# LP11F7826.net
KiCad netlist of a schematic drawn in EAGLE
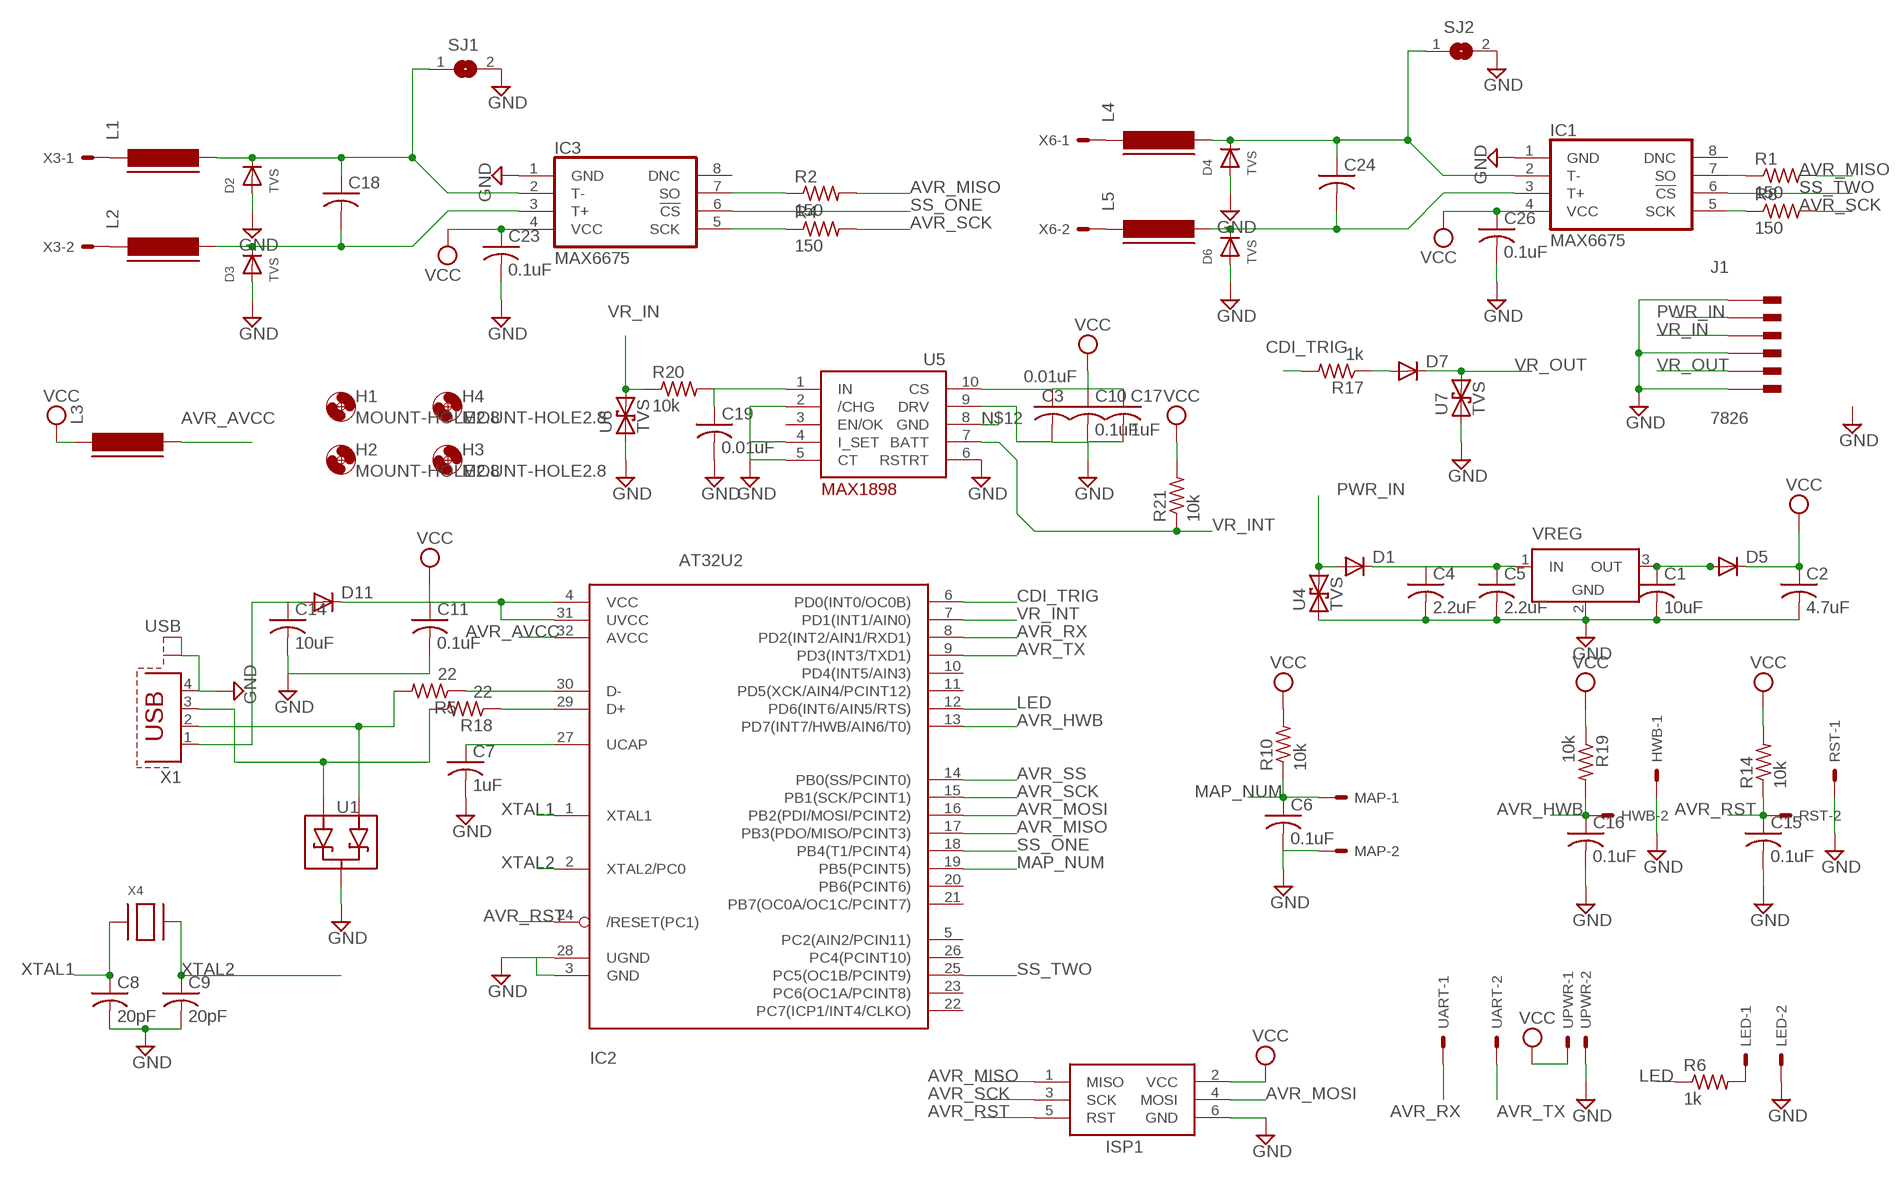
[diagram p0: schematic, sheet 1]

(export (version "E")
  (design (tool "Eeschema 10.0.6"))
  (components
    (comp (ref "C1")
      (value "10uF")
      (footprint "eagle-import:C1206")
      (libsource (lib "eagle-import") (part "C-USC1206"))
    )
    (comp (ref "C2")
      (value "4.7uF")
      (footprint "eagle-import:C1210")
      (libsource (lib "eagle-import") (part "C-USC1210"))
    )
    (comp (ref "C3")
      (value "0.01uF")
      (footprint "eagle-import:C0805")
      (libsource (lib "eagle-import") (part "C-USC0805"))
    )
    (comp (ref "C4")
      (value "2.2uF")
      (footprint "eagle-import:C1206")
      (libsource (lib "eagle-import") (part "C-USC1206"))
    )
    (comp (ref "C5")
      (value "2.2uF")
      (footprint "eagle-import:C1210")
      (libsource (lib "eagle-import") (part "C-USC1210"))
    )
    (comp (ref "C6")
      (value "0.1uF")
      (footprint "eagle-import:C0805")
      (libsource (lib "eagle-import") (part "C-USC0805"))
    )
    (comp (ref "C7")
      (value "1uF")
      (footprint "eagle-import:C0805")
      (libsource (lib "eagle-import") (part "C-USC0805"))
    )
    (comp (ref "C8")
      (value "20pF")
      (footprint "eagle-import:C0805")
      (libsource (lib "eagle-import") (part "C-USC0805"))
    )
    (comp (ref "C9")
      (value "20pF")
      (footprint "eagle-import:C0805")
      (libsource (lib "eagle-import") (part "C-USC0805"))
    )
    (comp (ref "C10")
      (value "0.1uF")
      (footprint "eagle-import:C0805")
      (libsource (lib "eagle-import") (part "C-USC0805"))
    )
    (comp (ref "C11")
      (value "0.1uF")
      (footprint "eagle-import:C0805")
      (libsource (lib "eagle-import") (part "C-USC0805"))
    )
    (comp (ref "C14")
      (value "10uF")
      (footprint "eagle-import:C0805")
      (libsource (lib "eagle-import") (part "C-USC0805"))
    )
    (comp (ref "C15")
      (value "0.1uF")
      (footprint "eagle-import:C0805")
      (libsource (lib "eagle-import") (part "C-USC0805"))
    )
    (comp (ref "C16")
      (value "0.1uF")
      (footprint "eagle-import:C0805")
      (libsource (lib "eagle-import") (part "C-USC0805"))
    )
    (comp (ref "C17")
      (value "1uF")
      (footprint "eagle-import:C0805")
      (libsource (lib "eagle-import") (part "C-USC0805"))
    )
    (comp (ref "C18")
      (value "C-USC0805")
      (footprint "eagle-import:C0805")
      (libsource (lib "eagle-import") (part "C-USC0805"))
    )
    (comp (ref "C19")
      (value "0.01uF")
      (footprint "eagle-import:C0805")
      (libsource (lib "eagle-import") (part "C-USC0805"))
    )
    (comp (ref "C23")
      (value "0.1uF")
      (footprint "eagle-import:C0805")
      (libsource (lib "eagle-import") (part "C-USC0805"))
    )
    (comp (ref "C24")
      (value "C-USC0805")
      (footprint "eagle-import:C0805")
      (libsource (lib "eagle-import") (part "C-USC0805"))
    )
    (comp (ref "C26")
      (value "0.1uF")
      (footprint "eagle-import:C0805")
      (libsource (lib "eagle-import") (part "C-USC0805"))
    )
    (comp (ref "D1")
      (value "CGRM4001-G")
      (footprint "eagle-import:SOD-123_MINI-SMA")
      (libsource (lib "eagle-import") (part "CGRM400-G1"))
    )
    (comp (ref "D2")
      (value "TVS")
      (footprint "eagle-import:SOD-323F")
      (libsource (lib "eagle-import") (part "DIODESOD-323F"))
    )
    (comp (ref "D3")
      (value "TVS")
      (footprint "eagle-import:SOD-323F")
      (libsource (lib "eagle-import") (part "DIODESOD-323F"))
    )
    (comp (ref "D4")
      (value "TVS")
      (footprint "eagle-import:SOD-323F")
      (libsource (lib "eagle-import") (part "DIODESOD-323F"))
    )
    (comp (ref "D5")
      (value "CGRM4001-G")
      (footprint "eagle-import:SOD-123_MINI-SMA")
      (libsource (lib "eagle-import") (part "CGRM400-G1"))
    )
    (comp (ref "D6")
      (value "TVS")
      (footprint "eagle-import:SOD-323F")
      (libsource (lib "eagle-import") (part "DIODESOD-323F"))
    )
    (comp (ref "D7")
      (value "CGRM4001-G")
      (footprint "eagle-import:SOD-123_MINI-SMA")
      (libsource (lib "eagle-import") (part "CGRM400-G1"))
    )
    (comp (ref "D11")
      (value "CGRM4001-G")
      (footprint "eagle-import:SOD-123_MINI-SMA")
      (libsource (lib "eagle-import") (part "CGRM400-G1"))
    )
    (comp (ref "H1")
      (value "MOUNT-HOLE2.8")
      (footprint "eagle-import:2,8")
      (libsource (lib "eagle-import") (part "MOUNT-HOLE2.8"))
    )
    (comp (ref "H2")
      (value "MOUNT-HOLE2.8")
      (footprint "eagle-import:2,8")
      (libsource (lib "eagle-import") (part "MOUNT-HOLE2.8"))
    )
    (comp (ref "H3")
      (value "MOUNT-HOLE2.8")
      (footprint "eagle-import:2,8")
      (libsource (lib "eagle-import") (part "MOUNT-HOLE2.8"))
    )
    (comp (ref "H4")
      (value "MOUNT-HOLE2.8")
      (footprint "eagle-import:2,8")
      (libsource (lib "eagle-import") (part "MOUNT-HOLE2.8"))
    )
    (comp (ref "HWB")
      (value "87758-0216")
      (footprint "eagle-import:87758-0216")
      (fields
        (field (name "MPN") "87758-0216")
        (field (name "OC_FARNELL") "unknown")
        (field (name "OC_NEWARK") "94M1513")
      )
      (libsource (lib "eagle-import") (part "87758-0216"))
    )
    (comp (ref "IC1")
      (value "MAX6675")
      (footprint "eagle-import:SO-8")
      (libsource (lib "eagle-import") (part "IC_MAX31855-SO-8"))
    )
    (comp (ref "IC2")
      (value "AT32U2")
      (footprint "eagle-import:TQFP32-08")
      (libsource (lib "eagle-import") (part "ATMEGA32U2-TQFP"))
    )
    (comp (ref "IC3")
      (value "MAX6675")
      (footprint "eagle-import:SO-8")
      (libsource (lib "eagle-import") (part "IC_MAX31855-SO-8"))
    )
    (comp (ref "ISP1")
      (value "AVRISP-6")
      (footprint "eagle-import:AVRISP")
      (libsource (lib "eagle-import") (part "AVRISP-6"))
    )
    (comp (ref "J1")
      (value "7826")
      (footprint "eagle-import:7806HEADER")
      (libsource (lib "eagle-import") (part "PIN262409-1"))
    )
    (comp (ref "L1")
      (value "FERRITE-0805")
      (footprint "eagle-import:FB805")
      (libsource (lib "eagle-import") (part "FERRITE-0805"))
    )
    (comp (ref "L2")
      (value "FERRITE-0805")
      (footprint "eagle-import:FB805")
      (libsource (lib "eagle-import") (part "FERRITE-0805"))
    )
    (comp (ref "L3")
      (value "FERRITE-0805")
      (footprint "eagle-import:FB805")
      (libsource (lib "eagle-import") (part "FERRITE-0805"))
    )
    (comp (ref "L4")
      (value "FERRITE-0805")
      (footprint "eagle-import:FB805")
      (libsource (lib "eagle-import") (part "FERRITE-0805"))
    )
    (comp (ref "L5")
      (value "FERRITE-0805")
      (footprint "eagle-import:FB805")
      (libsource (lib "eagle-import") (part "FERRITE-0805"))
    )
    (comp (ref "LED")
      (value "87758-0216")
      (footprint "eagle-import:87758-0216")
      (fields
        (field (name "MPN") "87758-0216")
        (field (name "OC_FARNELL") "unknown")
        (field (name "OC_NEWARK") "94M1513")
      )
      (libsource (lib "eagle-import") (part "87758-0216"))
    )
    (comp (ref "MAP")
      (value "87758-0216")
      (footprint "eagle-import:87758-0216")
      (libsource (lib "eagle-import") (part "87758-0216"))
    )
    (comp (ref "R1")
      (value "150")
      (footprint "eagle-import:R0805")
      (libsource (lib "eagle-import") (part "R-US_R0805"))
    )
    (comp (ref "R2")
      (value "150")
      (footprint "eagle-import:R0805")
      (libsource (lib "eagle-import") (part "R-US_R0805"))
    )
    (comp (ref "R4")
      (value "150")
      (footprint "eagle-import:R0805")
      (libsource (lib "eagle-import") (part "R-US_R0805"))
    )
    (comp (ref "R5")
      (value "22")
      (footprint "eagle-import:R0805")
      (libsource (lib "eagle-import") (part "R-US_R0805"))
    )
    (comp (ref "R6")
      (value "1k")
      (footprint "eagle-import:R0805")
      (libsource (lib "eagle-import") (part "R-US_R0805"))
    )
    (comp (ref "R8")
      (value "150")
      (footprint "eagle-import:R0805")
      (libsource (lib "eagle-import") (part "R-US_R0805"))
    )
    (comp (ref "R10")
      (value "10k")
      (footprint "eagle-import:R0805")
      (libsource (lib "eagle-import") (part "R-US_R0805"))
    )
    (comp (ref "R14")
      (value "10k")
      (footprint "eagle-import:R0805")
      (libsource (lib "eagle-import") (part "R-US_R0805"))
    )
    (comp (ref "R17")
      (value "1k")
      (footprint "eagle-import:R0805")
      (libsource (lib "eagle-import") (part "R-US_R0805"))
    )
    (comp (ref "R18")
      (value "22")
      (footprint "eagle-import:R0805")
      (libsource (lib "eagle-import") (part "R-US_R0805"))
    )
    (comp (ref "R19")
      (value "10k")
      (footprint "eagle-import:R0805")
      (libsource (lib "eagle-import") (part "R-US_R0805"))
    )
    (comp (ref "R20")
      (value "10k")
      (footprint "eagle-import:R0805")
      (libsource (lib "eagle-import") (part "R-US_R0805"))
    )
    (comp (ref "R21")
      (value "10k")
      (footprint "eagle-import:R0805")
      (libsource (lib "eagle-import") (part "R-US_R0805"))
    )
    (comp (ref "RST")
      (value "87758-0216")
      (footprint "eagle-import:87758-0216")
      (fields
        (field (name "MPN") "87758-0216")
        (field (name "OC_FARNELL") "unknown")
        (field (name "OC_NEWARK") "94M1513")
      )
      (libsource (lib "eagle-import") (part "87758-0216"))
    )
    (comp (ref "SJ1") (value "SJ") (footprint "eagle-import:SJ") (libsource (lib "eagle-import") (part "SJ")))
    (comp (ref "SJ2") (value "SJ") (footprint "eagle-import:SJ") (libsource (lib "eagle-import") (part "SJ")))
    (comp (ref "U1")
      (value "MMBZ27VCLT1")
      (footprint "eagle-import:SOT23-3")
      (libsource (lib "eagle-import") (part "MMBZ27VCLT1"))
    )
    (comp (ref "U4")
      (value "TVS")
      (footprint "eagle-import:SMA-DIODE")
      (libsource (lib "eagle-import") (part "TVS"))
    )
    (comp (ref "U5")
      (value "MAX9924")
      (footprint "eagle-import:UMAX10")
      (libsource (lib "eagle-import") (part "MAX1898U"))
    )
    (comp (ref "U6")
      (value "TVS")
      (footprint "eagle-import:SMA-DIODE")
      (libsource (lib "eagle-import") (part "TVS"))
    )
    (comp (ref "U7")
      (value "TVS")
      (footprint "eagle-import:SMA-DIODE")
      (libsource (lib "eagle-import") (part "TVS"))
    )
    (comp (ref "UART")
      (value "87758-0216")
      (footprint "eagle-import:87758-0216")
      (fields
        (field (name "MPN") "87758-0216")
        (field (name "OC_FARNELL") "unknown")
        (field (name "OC_NEWARK") "94M1513")
      )
      (libsource (lib "eagle-import") (part "87758-0216"))
    )
    (comp (ref "UPWR")
      (value "87758-0216")
      (footprint "eagle-import:87758-0216")
      (fields
        (field (name "MPN") "87758-0216")
        (field (name "OC_FARNELL") "unknown")
        (field (name "OC_NEWARK") "94M1513")
      )
      (libsource (lib "eagle-import") (part "87758-0216"))
    )
    (comp (ref "VREG")
      (value "LT1963EST-3.3")
      (footprint "eagle-import:SOT223")
      (libsource (lib "eagle-import") (part "LT1963EST-3.3"))
    )
    (comp (ref "X1")
      (value "USB")
      (footprint "eagle-import:PN61729-S")
      (libsource (lib "eagle-import") (part "PN61729-S"))
    )
    (comp (ref "X3")
      (value "22-23-2021")
      (footprint "eagle-import:22-23-2021")
      (fields
        (field (name "MF") "MOLEX")
        (field (name "MF_1") "MOLEX")
        (field (name "MPN") "22-23-2021")
        (field (name "OC_FARNELL") "1462926")
        (field (name "OC_NEWARK") "25C3832")
      )
      (libsource (lib "eagle-import") (part "22-23-2021"))
    )
    (comp (ref "X4")
      (value "XTALNX5032")
      (footprint "eagle-import:NX5032")
      (libsource (lib "eagle-import") (part "XTALNX5032"))
    )
    (comp (ref "X6")
      (value "22-23-2021")
      (footprint "eagle-import:22-23-2021")
      (fields
        (field (name "MF") "MOLEX")
        (field (name "MF_1") "MOLEX")
        (field (name "MPN") "22-23-2021")
        (field (name "OC_FARNELL") "1462926")
        (field (name "OC_NEWARK") "25C3832")
      )
      (libsource (lib "eagle-import") (part "22-23-2021"))
    )
  )
  (nets
    (net (code "1") (name "/AVR_AVCC") (class "Default")
      (node (ref "IC2") (pin "32") (pinfunction "AVCC_32") (pintype "bidirectional"))
      (node (ref "L3") (pin "2") (pinfunction "2_2") (pintype "passive"))
    )
    (net (code "2") (name "/AVR_HWB") (class "Default")
      (node (ref "C16") (pin "1") (pinfunction "1_1") (pintype "passive"))
      (node (ref "HWB") (pin "2") (pinfunction "S_2") (pintype "passive"))
      (node (ref "IC2") (pin "13") (pinfunction "PD7(INT7/HWB/AIN6/T0)_13") (pintype "bidirectional"))
      (node (ref "R19") (pin "2") (pinfunction "2_2") (pintype "passive"))
    )
    (net (code "3") (name "/AVR_MISO") (class "Default")
      (node (ref "IC2") (pin "17") (pinfunction "PB3(PDO/MISO/PCINT3)_17") (pintype "bidirectional"))
      (node (ref "ISP1") (pin "1") (pinfunction "MISO_1") (pintype "input"))
      (node (ref "R1") (pin "2") (pinfunction "2_2") (pintype "passive"))
      (node (ref "R2") (pin "2") (pinfunction "2_2") (pintype "passive"))
    )
    (net (code "4") (name "/AVR_MOSI") (class "Default")
      (node (ref "IC2") (pin "16") (pinfunction "PB2(PDI/MOSI/PCINT2)_16") (pintype "bidirectional"))
      (node (ref "ISP1") (pin "4") (pinfunction "MOSI_4") (pintype "output"))
    )
    (net (code "5") (name "/AVR_RST") (class "Default")
      (node (ref "C15") (pin "1") (pinfunction "1_1") (pintype "passive"))
      (node (ref "IC2") (pin "24") (pinfunction "/RESET(PC1)_24") (pintype "bidirectional"))
      (node (ref "ISP1") (pin "5") (pinfunction "RST_5") (pintype "output"))
      (node (ref "R14") (pin "1") (pinfunction "1_1") (pintype "passive"))
      (node (ref "RST") (pin "2") (pinfunction "S_2") (pintype "passive"))
    )
    (net (code "6") (name "/AVR_RX") (class "Default")
      (node (ref "IC2") (pin "8") (pinfunction "PD2(INT2/AIN1/RXD1)_8") (pintype "bidirectional"))
      (node (ref "UART") (pin "1") (pinfunction "S_1") (pintype "passive"))
    )
    (net (code "7") (name "/AVR_SCK") (class "Default")
      (node (ref "IC2") (pin "15") (pinfunction "PB1(SCK/PCINT1)_15") (pintype "bidirectional"))
      (node (ref "ISP1") (pin "3") (pinfunction "SCK_3") (pintype "output"))
      (node (ref "R4") (pin "2") (pinfunction "2_2") (pintype "passive"))
      (node (ref "R8") (pin "2") (pinfunction "2_2") (pintype "passive"))
    )
    (net (code "8") (name "/AVR_SS") (class "Default")
      (node (ref "IC2") (pin "14") (pinfunction "PB0(SS/PCINT0)_14") (pintype "bidirectional"))
    )
    (net (code "9") (name "/AVR_TX") (class "Default")
      (node (ref "IC2") (pin "9") (pinfunction "PD3(INT3/TXD1)_9") (pintype "bidirectional"))
      (node (ref "UART") (pin "2") (pinfunction "S_2") (pintype "passive"))
    )
    (net (code "10") (name "/CDI_TRIG") (class "Default")
      (node (ref "IC2") (pin "6") (pinfunction "PD0(INT0/OC0B)_6") (pintype "bidirectional"))
      (node (ref "R17") (pin "2") (pinfunction "2_2") (pintype "passive"))
    )
    (net (code "11") (name "/LED") (class "Default")
      (node (ref "IC2") (pin "12") (pinfunction "PD6(INT6/AIN5/RTS)_12") (pintype "bidirectional"))
      (node (ref "R6") (pin "1") (pinfunction "1_1") (pintype "passive"))
    )
    (net (code "12") (name "/MAP_NUM") (class "Default")
      (node (ref "C6") (pin "1") (pinfunction "1_1") (pintype "passive"))
      (node (ref "IC2") (pin "19") (pinfunction "PB5(PCINT5)_19") (pintype "bidirectional"))
      (node (ref "MAP") (pin "1") (pinfunction "S_1") (pintype "passive"))
      (node (ref "R10") (pin "1") (pinfunction "1_1") (pintype "passive"))
    )
    (net (code "13") (name "/N$12") (class "Default")
      (node (ref "U5") (pin "8") (pinfunction "GND_8") (pintype "power_in"))
    )
    (net (code "14") (name "/PWR_IN") (class "Default")
      (node (ref "D1") (pin "A") (pinfunction "A_A") (pintype "passive"))
      (node (ref "J1") (pin "A10") (pinfunction "5_A10") (pintype "passive"))
      (node (ref "J1") (pin "A9") (pinfunction "5_A9") (pintype "passive"))
      (node (ref "U4") (pin "C") (pinfunction "2_C") (pintype "passive"))
    )
    (net (code "15") (name "/SS_ONE") (class "Default")
      (node (ref "IC2") (pin "18") (pinfunction "PB4(T1/PCINT4)_18") (pintype "bidirectional"))
      (node (ref "IC3") (pin "6") (pinfunction "~{CS}_6") (pintype "input"))
    )
    (net (code "16") (name "/SS_TWO") (class "Default")
      (node (ref "IC1") (pin "6") (pinfunction "~{CS}_6") (pintype "input"))
      (node (ref "IC2") (pin "25") (pinfunction "PC5(OC1B/PCINT9)_25") (pintype "bidirectional"))
    )
    (net (code "17") (name "/VR_IN") (class "Default")
      (node (ref "J1") (pin "A7") (pinfunction "4_A7") (pintype "passive"))
      (node (ref "J1") (pin "A8") (pinfunction "4_A8") (pintype "passive"))
      (node (ref "R20") (pin "1") (pinfunction "1_1") (pintype "passive"))
      (node (ref "U6") (pin "C") (pinfunction "2_C") (pintype "passive"))
    )
    (net (code "18") (name "/VR_INT") (class "Default")
      (node (ref "IC2") (pin "7") (pinfunction "PD1(INT1/AIN0)_7") (pintype "bidirectional"))
      (node (ref "R21") (pin "1") (pinfunction "1_1") (pintype "passive"))
      (node (ref "U5") (pin "7") (pinfunction "BATT_7") (pintype "output"))
    )
    (net (code "19") (name "/VR_OUT") (class "Default")
      (node (ref "D7") (pin "C") (pinfunction "C_C") (pintype "passive"))
      (node (ref "J1") (pin "A3") (pinfunction "2_A3") (pintype "passive"))
      (node (ref "J1") (pin "A4") (pinfunction "2_A4") (pintype "passive"))
      (node (ref "U7") (pin "C") (pinfunction "2_C") (pintype "passive"))
    )
    (net (code "20") (name "/XTAL1") (class "Default")
      (node (ref "C8") (pin "1") (pinfunction "1_1") (pintype "passive"))
      (node (ref "IC2") (pin "1") (pinfunction "XTAL1_1") (pintype "bidirectional"))
      (node (ref "X4") (pin "P$1") (pinfunction "P$1_P$1") (pintype "bidirectional"))
    )
    (net (code "21") (name "/XTAL2") (class "Default")
      (node (ref "C9") (pin "1") (pinfunction "1_1") (pintype "passive"))
      (node (ref "IC2") (pin "2") (pinfunction "XTAL2/PC0_2") (pintype "bidirectional"))
      (node (ref "X4") (pin "P$2") (pinfunction "P$2_P$2") (pintype "bidirectional"))
    )
    (net (code "22") (name "GND") (class "Default")
      (node (ref "C1") (pin "2") (pinfunction "2_2") (pintype "passive"))
      (node (ref "C10") (pin "2") (pinfunction "2_2") (pintype "passive"))
      (node (ref "C11") (pin "2") (pinfunction "2_2") (pintype "passive"))
      (node (ref "C14") (pin "2") (pinfunction "2_2") (pintype "passive"))
      (node (ref "C15") (pin "2") (pinfunction "2_2") (pintype "passive"))
      (node (ref "C16") (pin "2") (pinfunction "2_2") (pintype "passive"))
      (node (ref "C17") (pin "2") (pinfunction "2_2") (pintype "passive"))
      (node (ref "C19") (pin "2") (pinfunction "2_2") (pintype "passive"))
      (node (ref "C2") (pin "2") (pinfunction "2_2") (pintype "passive"))
      (node (ref "C23") (pin "2") (pinfunction "2_2") (pintype "passive"))
      (node (ref "C26") (pin "2") (pinfunction "2_2") (pintype "passive"))
      (node (ref "C3") (pin "2") (pinfunction "2_2") (pintype "passive"))
      (node (ref "C4") (pin "2") (pinfunction "2_2") (pintype "passive"))
      (node (ref "C5") (pin "2") (pinfunction "2_2") (pintype "passive"))
      (node (ref "C6") (pin "2") (pinfunction "2_2") (pintype "passive"))
      (node (ref "C7") (pin "2") (pinfunction "2_2") (pintype "passive"))
      (node (ref "C8") (pin "2") (pinfunction "2_2") (pintype "passive"))
      (node (ref "C9") (pin "2") (pinfunction "2_2") (pintype "passive"))
      (node (ref "D2") (pin "A") (pinfunction "A_A") (pintype "passive"))
      (node (ref "D3") (pin "A") (pinfunction "A_A") (pintype "passive"))
      (node (ref "D4") (pin "A") (pinfunction "A_A") (pintype "passive"))
      (node (ref "D6") (pin "A") (pinfunction "A_A") (pintype "passive"))
      (node (ref "HWB") (pin "1") (pinfunction "S_1") (pintype "passive"))
      (node (ref "IC1") (pin "1") (pinfunction "GND_1") (pintype "power_in"))
      (node (ref "IC2") (pin "28") (pinfunction "UGND_28") (pintype "bidirectional"))
      (node (ref "IC2") (pin "3") (pinfunction "GND_3") (pintype "bidirectional"))
      (node (ref "IC3") (pin "1") (pinfunction "GND_1") (pintype "power_in"))
      (node (ref "ISP1") (pin "6") (pinfunction "GND_6") (pintype "power_in"))
      (node (ref "J1") (pin "A1") (pinfunction "1_A1") (pintype "passive"))
      (node (ref "J1") (pin "A11") (pinfunction "6_A11") (pintype "passive"))
      (node (ref "J1") (pin "A12") (pinfunction "6_A12") (pintype "passive"))
      (node (ref "J1") (pin "A2") (pinfunction "1_A2") (pintype "passive"))
      (node (ref "J1") (pin "A5") (pinfunction "3_A5") (pintype "passive"))
      (node (ref "J1") (pin "A6") (pinfunction "3_A6") (pintype "passive"))
      (node (ref "LED") (pin "2") (pinfunction "S_2") (pintype "passive"))
      (node (ref "MAP") (pin "2") (pinfunction "S_2") (pintype "passive"))
      (node (ref "RST") (pin "1") (pinfunction "S_1") (pintype "passive"))
      (node (ref "SJ1") (pin "2") (pinfunction "2_2") (pintype "passive"))
      (node (ref "SJ2") (pin "2") (pinfunction "2_2") (pintype "passive"))
      (node (ref "U1") (pin "3") (pinfunction "C_3") (pintype "passive"))
      (node (ref "U4") (pin "A") (pinfunction "1_A") (pintype "passive"))
      (node (ref "U5") (pin "2") (pinfunction "/CHG_2") (pintype "output"))
      (node (ref "U5") (pin "4") (pinfunction "I_SET_4") (pintype "passive"))
      (node (ref "U5") (pin "5") (pinfunction "CT_5") (pintype "passive"))
      (node (ref "U5") (pin "6") (pinfunction "RSTRT_6") (pintype "passive"))
      (node (ref "U5") (pin "9") (pinfunction "DRV_9") (pintype "output"))
      (node (ref "U6") (pin "A") (pinfunction "1_A") (pintype "passive"))
      (node (ref "U7") (pin "A") (pinfunction "1_A") (pintype "passive"))
      (node (ref "UPWR") (pin "2") (pinfunction "S_2") (pintype "passive"))
      (node (ref "VREG") (pin "2") (pinfunction "GND_2") (pintype "power_in"))
      (node (ref "X1") (pin "4") (pinfunction "4_4") (pintype "passive"))
      (node (ref "X1") (pin "S1") (pinfunction "S1_S1") (pintype "passive"))
      (node (ref "X1") (pin "S2") (pinfunction "S2_S2") (pintype "passive"))
    )
    (net (code "23") (name "Net-(C14-Pad1)") (class "Default")
      (node (ref "C14") (pin "1") (pinfunction "1_1") (pintype "passive"))
      (node (ref "D11") (pin "A") (pinfunction "A_A") (pintype "passive"))
      (node (ref "X1") (pin "1") (pinfunction "1_1") (pintype "passive"))
    )
    (net (code "24") (name "Net-(D7-PadA)") (class "Default")
      (node (ref "D7") (pin "A") (pinfunction "A_A") (pintype "passive"))
      (node (ref "R17") (pin "1") (pinfunction "1_1") (pintype "passive"))
    )
    (net (code "25") (name "Net-(IC1-SCK)") (class "Default")
      (node (ref "IC1") (pin "5") (pinfunction "SCK_5") (pintype "input"))
      (node (ref "R8") (pin "1") (pinfunction "1_1") (pintype "passive"))
    )
    (net (code "26") (name "Net-(IC1-SO)") (class "Default")
      (node (ref "IC1") (pin "7") (pinfunction "SO_7") (pintype "output"))
      (node (ref "R1") (pin "1") (pinfunction "1_1") (pintype "passive"))
    )
    (net (code "27") (name "Net-(IC1-T+)") (class "Default")
      (node (ref "C24") (pin "2") (pinfunction "2_2") (pintype "passive"))
      (node (ref "D6") (pin "C") (pinfunction "C_C") (pintype "passive"))
      (node (ref "IC1") (pin "3") (pinfunction "T+_3") (pintype "input"))
      (node (ref "L5") (pin "2") (pinfunction "2_2") (pintype "passive"))
    )
    (net (code "28") (name "Net-(IC1-T-)") (class "Default")
      (node (ref "C24") (pin "1") (pinfunction "1_1") (pintype "passive"))
      (node (ref "D4") (pin "C") (pinfunction "C_C") (pintype "passive"))
      (node (ref "IC1") (pin "2") (pinfunction "T-_2") (pintype "input"))
      (node (ref "L4") (pin "2") (pinfunction "2_2") (pintype "passive"))
      (node (ref "SJ2") (pin "1") (pinfunction "1_1") (pintype "passive"))
    )
    (net (code "29") (name "Net-(IC2-D+)") (class "Default")
      (node (ref "IC2") (pin "29") (pinfunction "D+_29") (pintype "bidirectional"))
      (node (ref "R18") (pin "1") (pinfunction "1_1") (pintype "passive"))
    )
    (net (code "30") (name "Net-(IC2-D-)") (class "Default")
      (node (ref "IC2") (pin "30") (pinfunction "D-_30") (pintype "bidirectional"))
      (node (ref "R5") (pin "1") (pinfunction "1_1") (pintype "passive"))
    )
    (net (code "31") (name "Net-(IC2-UCAP)") (class "Default")
      (node (ref "C7") (pin "1") (pinfunction "1_1") (pintype "passive"))
      (node (ref "IC2") (pin "27") (pinfunction "UCAP_27") (pintype "bidirectional"))
    )
    (net (code "32") (name "Net-(IC3-SCK)") (class "Default")
      (node (ref "IC3") (pin "5") (pinfunction "SCK_5") (pintype "input"))
      (node (ref "R4") (pin "1") (pinfunction "1_1") (pintype "passive"))
    )
    (net (code "33") (name "Net-(IC3-SO)") (class "Default")
      (node (ref "IC3") (pin "7") (pinfunction "SO_7") (pintype "output"))
      (node (ref "R2") (pin "1") (pinfunction "1_1") (pintype "passive"))
    )
    (net (code "34") (name "Net-(IC3-T+)") (class "Default")
      (node (ref "C18") (pin "2") (pinfunction "2_2") (pintype "passive"))
      (node (ref "D3") (pin "C") (pinfunction "C_C") (pintype "passive"))
      (node (ref "IC3") (pin "3") (pinfunction "T+_3") (pintype "input"))
      (node (ref "L2") (pin "2") (pinfunction "2_2") (pintype "passive"))
    )
    (net (code "35") (name "Net-(IC3-T-)") (class "Default")
      (node (ref "C18") (pin "1") (pinfunction "1_1") (pintype "passive"))
      (node (ref "D2") (pin "C") (pinfunction "C_C") (pintype "passive"))
      (node (ref "IC3") (pin "2") (pinfunction "T-_2") (pintype "input"))
      (node (ref "L1") (pin "2") (pinfunction "2_2") (pintype "passive"))
      (node (ref "SJ1") (pin "1") (pinfunction "1_1") (pintype "passive"))
    )
    (net (code "36") (name "Net-(LEDA-S)") (class "Default")
      (node (ref "LED") (pin "1") (pinfunction "S_1") (pintype "passive"))
      (node (ref "R6") (pin "2") (pinfunction "2_2") (pintype "passive"))
    )
    (net (code "37") (name "Net-(U1-A1)") (class "Default")
      (node (ref "R5") (pin "2") (pinfunction "2_2") (pintype "passive"))
      (node (ref "U1") (pin "1") (pinfunction "A1_1") (pintype "passive"))
      (node (ref "X1") (pin "2") (pinfunction "2_2") (pintype "passive"))
    )
    (net (code "38") (name "Net-(U1-A2)") (class "Default")
      (node (ref "R18") (pin "2") (pinfunction "2_2") (pintype "passive"))
      (node (ref "U1") (pin "2") (pinfunction "A2_2") (pintype "passive"))
      (node (ref "X1") (pin "3") (pinfunction "3_3") (pintype "passive"))
    )
    (net (code "39") (name "Net-(U5-IN)") (class "Default")
      (node (ref "C19") (pin "1") (pinfunction "1_1") (pintype "passive"))
      (node (ref "R20") (pin "2") (pinfunction "2_2") (pintype "passive"))
      (node (ref "U5") (pin "1") (pinfunction "IN_1") (pintype "input"))
    )
    (net (code "40") (name "Net-(VREGA-IN)") (class "Default")
      (node (ref "C4") (pin "1") (pinfunction "1_1") (pintype "passive"))
      (node (ref "C5") (pin "1") (pinfunction "1_1") (pintype "passive"))
      (node (ref "D1") (pin "C") (pinfunction "C_C") (pintype "passive"))
      (node (ref "VREG") (pin "1") (pinfunction "IN_1") (pintype "input"))
    )
    (net (code "41") (name "Net-(VREGA-OUT)") (class "Default")
      (node (ref "C1") (pin "1") (pinfunction "1_1") (pintype "passive"))
      (node (ref "D5") (pin "A") (pinfunction "A_A") (pintype "passive"))
      (node (ref "VREG") (pin "3") (pinfunction "OUT_3") (pintype "output"))
    )
    (net (code "42") (name "Net-(X3A-S)") (class "Default")
      (node (ref "L1") (pin "1") (pinfunction "1_1") (pintype "passive"))
      (node (ref "X3") (pin "1") (pinfunction "S_1") (pintype "passive"))
    )
    (net (code "43") (name "Net-(X3B-S)") (class "Default")
      (node (ref "L2") (pin "1") (pinfunction "1_1") (pintype "passive"))
      (node (ref "X3") (pin "2") (pinfunction "S_2") (pintype "passive"))
    )
    (net (code "44") (name "Net-(X6A-S)") (class "Default")
      (node (ref "L4") (pin "1") (pinfunction "1_1") (pintype "passive"))
      (node (ref "X6") (pin "1") (pinfunction "S_1") (pintype "passive"))
    )
    (net (code "45") (name "Net-(X6B-S)") (class "Default")
      (node (ref "L5") (pin "1") (pinfunction "1_1") (pintype "passive"))
      (node (ref "X6") (pin "2") (pinfunction "S_2") (pintype "passive"))
    )
    (net (code "46") (name "VCC") (class "Default")
      (node (ref "C10") (pin "1") (pinfunction "1_1") (pintype "passive"))
      (node (ref "C11") (pin "1") (pinfunction "1_1") (pintype "passive"))
      (node (ref "C17") (pin "1") (pinfunction "1_1") (pintype "passive"))
      (node (ref "C2") (pin "1") (pinfunction "1_1") (pintype "passive"))
      (node (ref "C23") (pin "1") (pinfunction "1_1") (pintype "passive"))
      (node (ref "C26") (pin "1") (pinfunction "1_1") (pintype "passive"))
      (node (ref "C3") (pin "1") (pinfunction "1_1") (pintype "passive"))
      (node (ref "D11") (pin "C") (pinfunction "C_C") (pintype "passive"))
      (node (ref "D5") (pin "C") (pinfunction "C_C") (pintype "passive"))
      (node (ref "IC1") (pin "4") (pinfunction "VCC_4") (pintype "power_in"))
      (node (ref "IC2") (pin "31") (pinfunction "UVCC_31") (pintype "bidirectional"))
      (node (ref "IC2") (pin "4") (pinfunction "VCC_4") (pintype "bidirectional"))
      (node (ref "IC3") (pin "4") (pinfunction "VCC_4") (pintype "power_in"))
      (node (ref "ISP1") (pin "2") (pinfunction "VCC_2") (pintype "power_in"))
      (node (ref "L3") (pin "1") (pinfunction "1_1") (pintype "passive"))
      (node (ref "R10") (pin "2") (pinfunction "2_2") (pintype "passive"))
      (node (ref "R14") (pin "2") (pinfunction "2_2") (pintype "passive"))
      (node (ref "R19") (pin "1") (pinfunction "1_1") (pintype "passive"))
      (node (ref "R21") (pin "2") (pinfunction "2_2") (pintype "passive"))
      (node (ref "U5") (pin "10") (pinfunction "CS_10") (pintype "input"))
      (node (ref "UPWR") (pin "1") (pinfunction "S_1") (pintype "passive"))
    )
    (net (code "47") (name "unconnected-(IC1-DNC-Pad8)") (class "Default")
      (node (ref "IC1") (pin "8") (pinfunction "DNC_8") (pintype "no_connect"))
    )
    (net (code "48") (name "unconnected-(IC2-PB6(PCINT6)-Pad20)") (class "Default")
      (node (ref "IC2") (pin "20") (pinfunction "PB6(PCINT6)_20") (pintype "bidirectional"))
    )
    (net (code "49") (name "unconnected-(IC2-PB7(OC0A{slash}OC1C{slash}PCINT7)-Pad21)") (class "Default")
      (node (ref "IC2") (pin "21") (pinfunction "PB7(OC0A/OC1C/PCINT7)_21") (pintype "bidirectional"))
    )
    (net (code "50") (name "unconnected-(IC2-PC2(AIN2{slash}PCIN11)-Pad5)") (class "Default")
      (node (ref "IC2") (pin "5") (pinfunction "PC2(AIN2/PCIN11)_5") (pintype "bidirectional"))
    )
    (net (code "51") (name "unconnected-(IC2-PC4(PCINT10)-Pad26)") (class "Default")
      (node (ref "IC2") (pin "26") (pinfunction "PC4(PCINT10)_26") (pintype "bidirectional"))
    )
    (net (code "52") (name "unconnected-(IC2-PC6(OC1A{slash}PCINT8)-Pad23)") (class "Default")
      (node (ref "IC2") (pin "23") (pinfunction "PC6(OC1A/PCINT8)_23") (pintype "bidirectional"))
    )
    (net (code "53") (name "unconnected-(IC2-PC7(ICP1{slash}INT4{slash}CLKO)-Pad22)") (class "Default")
      (node (ref "IC2") (pin "22") (pinfunction "PC7(ICP1/INT4/CLKO)_22") (pintype "bidirectional"))
    )
    (net (code "54") (name "unconnected-(IC2-PD4(INT5{slash}AIN3)-Pad10)") (class "Default")
      (node (ref "IC2") (pin "10") (pinfunction "PD4(INT5/AIN3)_10") (pintype "bidirectional"))
    )
    (net (code "55") (name "unconnected-(IC2-PD5(XCK{slash}AIN4{slash}PCINT12)-Pad11)") (class "Default")
      (node (ref "IC2") (pin "11") (pinfunction "PD5(XCK/AIN4/PCINT12)_11") (pintype "bidirectional"))
    )
    (net (code "56") (name "unconnected-(IC3-DNC-Pad8)") (class "Default")
      (node (ref "IC3") (pin "8") (pinfunction "DNC_8") (pintype "no_connect"))
    )
    (net (code "57") (name "unconnected-(U5-EN{slash}OK-Pad3)") (class "Default")
      (node (ref "U5") (pin "3") (pinfunction "EN/OK_3") (pintype "input"))
    )
  )
)
